# SwitchBoard_MP3.net
KiCad netlist of a schematic drawn in EAGLE
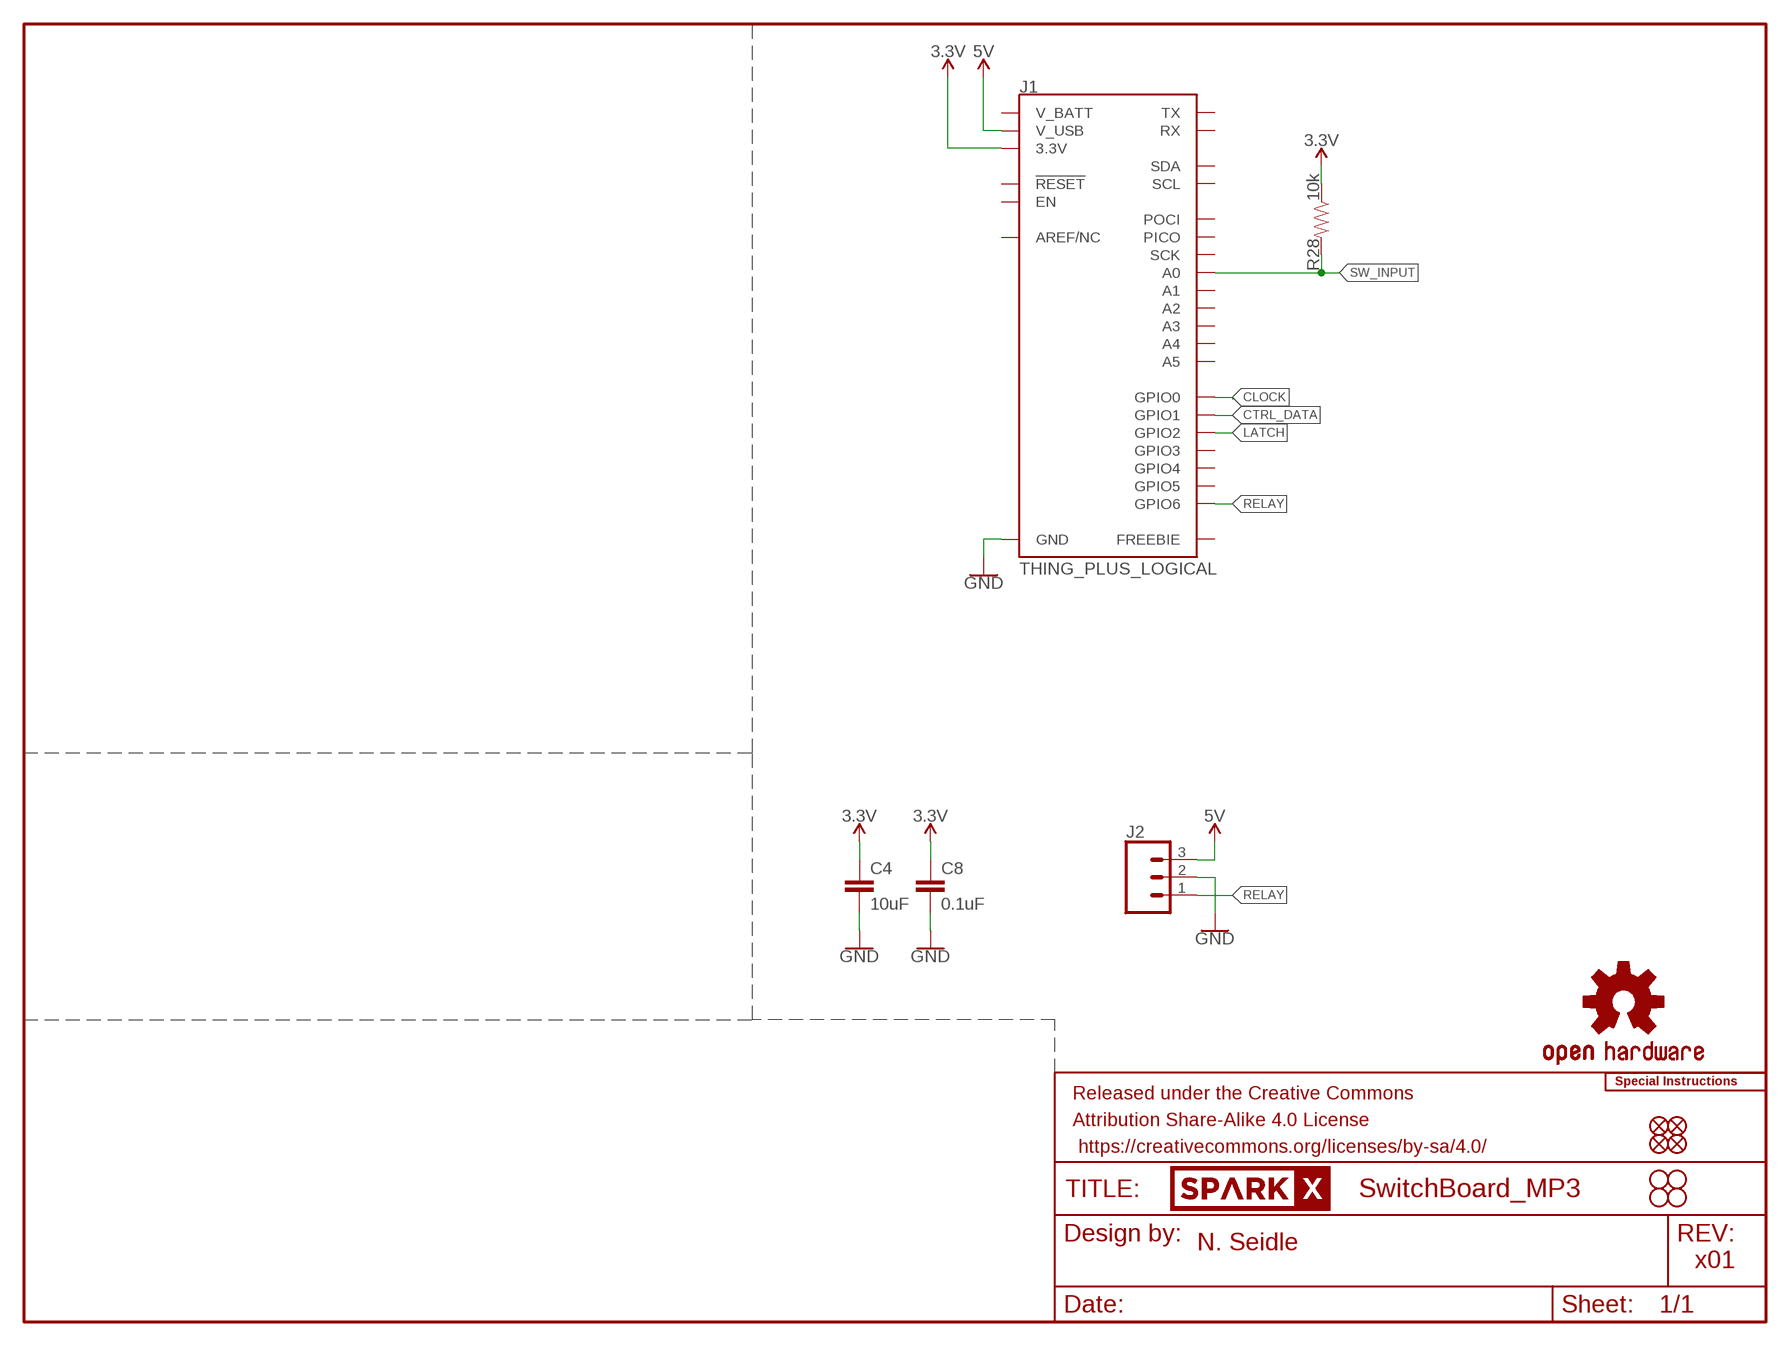
[diagram p0: schematic, sheet 1, part 1 of 2]
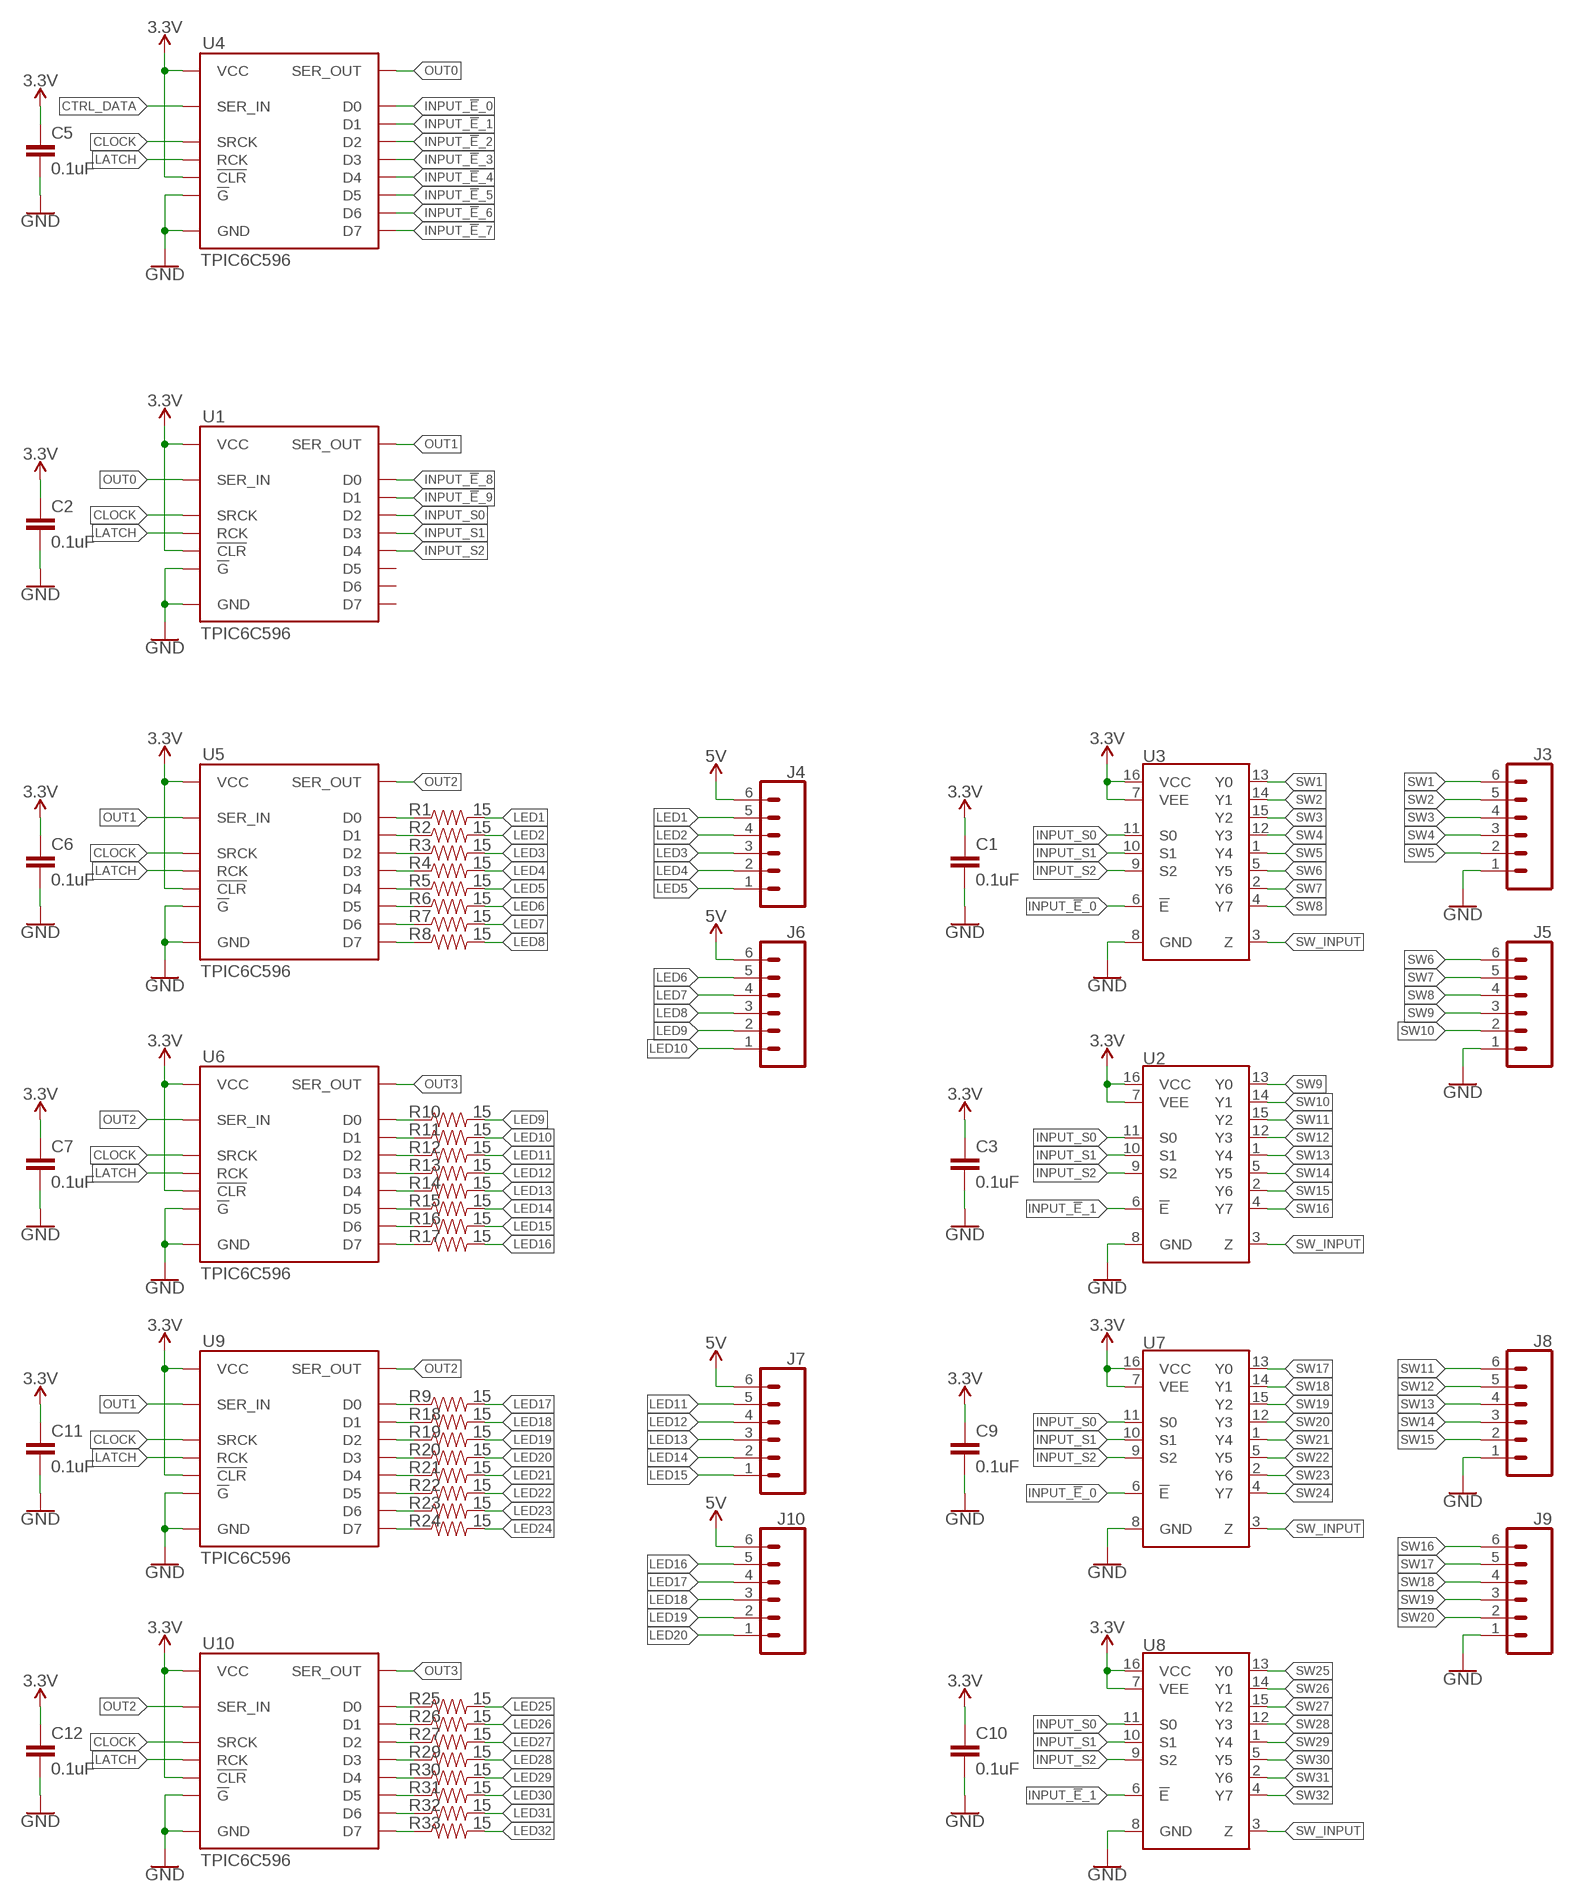
[diagram p1: schematic, sheet 1, part 2 of 2]

(export (version "E")
  (design (tool "Eeschema 10.0.6"))
  (components
    (comp (ref "C1")
      (value "0.1uF")
      (footprint "eagle-import:0603")
      (libsource (lib "eagle-import") (part "0.1UF-0603-25V-10%-X7R-WE"))
    )
    (comp (ref "C2")
      (value "0.1uF")
      (footprint "eagle-import:0603")
      (libsource (lib "eagle-import") (part "0.1UF-0603-25V-10%-X7R-WE"))
    )
    (comp (ref "C3")
      (value "0.1uF")
      (footprint "eagle-import:0603")
      (libsource (lib "eagle-import") (part "0.1UF-0603-25V-10%-X7R-WE"))
    )
    (comp (ref "C4")
      (value "10uF")
      (footprint "eagle-import:0805")
      (libsource (lib "eagle-import") (part "10UF-0805-25V-10%"))
    )
    (comp (ref "C5")
      (value "0.1uF")
      (footprint "eagle-import:0603")
      (libsource (lib "eagle-import") (part "0.1UF-0603-25V-10%-X7R-WE"))
    )
    (comp (ref "C6")
      (value "0.1uF")
      (footprint "eagle-import:0603")
      (libsource (lib "eagle-import") (part "0.1UF-0603-25V-10%-X7R-WE"))
    )
    (comp (ref "C7")
      (value "0.1uF")
      (footprint "eagle-import:0603")
      (libsource (lib "eagle-import") (part "0.1UF-0603-25V-10%-X7R-WE"))
    )
    (comp (ref "C8")
      (value "0.1uF")
      (footprint "eagle-import:0603")
      (libsource (lib "eagle-import") (part "0.1UF-0603-25V-10%-X7R-WE"))
    )
    (comp (ref "C9")
      (value "0.1uF")
      (footprint "eagle-import:0603")
      (libsource (lib "eagle-import") (part "0.1UF-0603-25V-10%-X7R-WE"))
    )
    (comp (ref "C10")
      (value "0.1uF")
      (footprint "eagle-import:0603")
      (libsource (lib "eagle-import") (part "0.1UF-0603-25V-10%-X7R-WE"))
    )
    (comp (ref "C11")
      (value "0.1uF")
      (footprint "eagle-import:0603")
      (libsource (lib "eagle-import") (part "0.1UF-0603-25V-10%-X7R-WE"))
    )
    (comp (ref "C12")
      (value "0.1uF")
      (footprint "eagle-import:0603")
      (libsource (lib "eagle-import") (part "0.1UF-0603-25V-10%-X7R-WE"))
    )
    (comp (ref "FD1")
      (value "FIDUCIAL1X2")
      (footprint "eagle-import:FIDUCIAL-1X2")
      (libsource (lib "eagle-import") (part "FIDUCIAL1X2"))
    )
    (comp (ref "FD2")
      (value "FIDUCIAL1X2")
      (footprint "eagle-import:FIDUCIAL-1X2")
      (libsource (lib "eagle-import") (part "FIDUCIAL1X2"))
    )
    (comp (ref "FD3")
      (value "FIDUCIAL1X2")
      (footprint "eagle-import:FIDUCIAL-1X2")
      (libsource (lib "eagle-import") (part "FIDUCIAL1X2"))
    )
    (comp (ref "FD4")
      (value "FIDUCIAL1X2")
      (footprint "eagle-import:FIDUCIAL-1X2")
      (libsource (lib "eagle-import") (part "FIDUCIAL1X2"))
    )
    (comp (ref "FRAME1")
      (value "FRAME-LETTER")
      (footprint "eagle-import:CREATIVE_COMMONS")
      (libsource (lib "eagle-import") (part "FRAME-LETTER"))
    )
    (comp (ref "H1")
      (value "STAND-OFF")
      (footprint "eagle-import:STAND-OFF")
      (libsource (lib "eagle-import") (part "STAND-OFF"))
    )
    (comp (ref "H2")
      (value "STAND-OFF")
      (footprint "eagle-import:STAND-OFF")
      (libsource (lib "eagle-import") (part "STAND-OFF"))
    )
    (comp (ref "H3")
      (value "STAND-OFF")
      (footprint "eagle-import:STAND-OFF")
      (libsource (lib "eagle-import") (part "STAND-OFF"))
    )
    (comp (ref "H4")
      (value "STAND-OFF")
      (footprint "eagle-import:STAND-OFF")
      (libsource (lib "eagle-import") (part "STAND-OFF"))
    )
    (comp (ref "J1")
      (value "THING_PLUS_LOGICAL")
      (footprint "eagle-import:THING_PLUS")
      (libsource (lib "eagle-import") (part "THING_PLUS_LOGICAL"))
    )
    (comp (ref "J2")
      (value "CONN_03JST-PTH-NS")
      (footprint "eagle-import:JST-3-PTH-NS")
      (libsource (lib "eagle-import") (part "CONN_03JST-PTH-NS"))
    )
    (comp (ref "J3")
      (value "CONN_06JST-SMD-LOCKING")
      (footprint "eagle-import:JST-6-SMD-1.25MM-LOCKING")
      (libsource (lib "eagle-import") (part "CONN_06JST-SMD-LOCKING"))
    )
    (comp (ref "J4")
      (value "CONN_06JST-SMD-LOCKING")
      (footprint "eagle-import:JST-6-SMD-1.25MM-LOCKING")
      (libsource (lib "eagle-import") (part "CONN_06JST-SMD-LOCKING"))
    )
    (comp (ref "J5")
      (value "CONN_06JST-SMD-LOCKING")
      (footprint "eagle-import:JST-6-SMD-1.25MM-LOCKING")
      (libsource (lib "eagle-import") (part "CONN_06JST-SMD-LOCKING"))
    )
    (comp (ref "J6")
      (value "CONN_06JST-SMD-LOCKING")
      (footprint "eagle-import:JST-6-SMD-1.25MM-LOCKING")
      (libsource (lib "eagle-import") (part "CONN_06JST-SMD-LOCKING"))
    )
    (comp (ref "J7")
      (value "CONN_06JST-SMD-LOCKING")
      (footprint "eagle-import:JST-6-SMD-1.25MM-LOCKING")
      (libsource (lib "eagle-import") (part "CONN_06JST-SMD-LOCKING"))
    )
    (comp (ref "J8")
      (value "CONN_06JST-SMD-LOCKING")
      (footprint "eagle-import:JST-6-SMD-1.25MM-LOCKING")
      (libsource (lib "eagle-import") (part "CONN_06JST-SMD-LOCKING"))
    )
    (comp (ref "J9")
      (value "CONN_06JST-SMD-LOCKING")
      (footprint "eagle-import:JST-6-SMD-1.25MM-LOCKING")
      (libsource (lib "eagle-import") (part "CONN_06JST-SMD-LOCKING"))
    )
    (comp (ref "J10")
      (value "CONN_06JST-SMD-LOCKING")
      (footprint "eagle-import:JST-6-SMD-1.25MM-LOCKING")
      (libsource (lib "eagle-import") (part "CONN_06JST-SMD-LOCKING"))
    )
    (comp (ref "LOGO1")
      (value "SPECIAL_INSTRUCTIONS-ORDERING")
      (footprint "eagle-import:ORDERING_INSTRUCTIONS")
      (libsource (lib "eagle-import") (part "SPECIAL_INSTRUCTIONS-ORDERING"))
    )
    (comp (ref "LOGO2")
      (value "OSHW-LOGOS")
      (footprint "eagle-import:OSHW-LOGO-S")
      (libsource (lib "eagle-import") (part "OSHW-LOGOS"))
    )
    (comp (ref "R1")
      (value "15")
      (footprint "eagle-import:0603")
      (libsource (lib "eagle-import") (part "15OHM-0603-1/10W-1%"))
    )
    (comp (ref "R2")
      (value "15")
      (footprint "eagle-import:0603")
      (libsource (lib "eagle-import") (part "15OHM-0603-1/10W-1%"))
    )
    (comp (ref "R3")
      (value "15")
      (footprint "eagle-import:0603")
      (libsource (lib "eagle-import") (part "15OHM-0603-1/10W-1%"))
    )
    (comp (ref "R4")
      (value "15")
      (footprint "eagle-import:0603")
      (libsource (lib "eagle-import") (part "15OHM-0603-1/10W-1%"))
    )
    (comp (ref "R5")
      (value "15")
      (footprint "eagle-import:0603")
      (libsource (lib "eagle-import") (part "15OHM-0603-1/10W-1%"))
    )
    (comp (ref "R6")
      (value "15")
      (footprint "eagle-import:0603")
      (libsource (lib "eagle-import") (part "15OHM-0603-1/10W-1%"))
    )
    (comp (ref "R7")
      (value "15")
      (footprint "eagle-import:0603")
      (libsource (lib "eagle-import") (part "15OHM-0603-1/10W-1%"))
    )
    (comp (ref "R8")
      (value "15")
      (footprint "eagle-import:0603")
      (libsource (lib "eagle-import") (part "15OHM-0603-1/10W-1%"))
    )
    (comp (ref "R9")
      (value "15")
      (footprint "eagle-import:0603")
      (libsource (lib "eagle-import") (part "15OHM-0603-1/10W-1%"))
    )
    (comp (ref "R10")
      (value "15")
      (footprint "eagle-import:0603")
      (libsource (lib "eagle-import") (part "15OHM-0603-1/10W-1%"))
    )
    (comp (ref "R11")
      (value "15")
      (footprint "eagle-import:0603")
      (libsource (lib "eagle-import") (part "15OHM-0603-1/10W-1%"))
    )
    (comp (ref "R12")
      (value "15")
      (footprint "eagle-import:0603")
      (libsource (lib "eagle-import") (part "15OHM-0603-1/10W-1%"))
    )
    (comp (ref "R13")
      (value "15")
      (footprint "eagle-import:0603")
      (libsource (lib "eagle-import") (part "15OHM-0603-1/10W-1%"))
    )
    (comp (ref "R14")
      (value "15")
      (footprint "eagle-import:0603")
      (libsource (lib "eagle-import") (part "15OHM-0603-1/10W-1%"))
    )
    (comp (ref "R15")
      (value "15")
      (footprint "eagle-import:0603")
      (libsource (lib "eagle-import") (part "15OHM-0603-1/10W-1%"))
    )
    (comp (ref "R16")
      (value "15")
      (footprint "eagle-import:0603")
      (libsource (lib "eagle-import") (part "15OHM-0603-1/10W-1%"))
    )
    (comp (ref "R17")
      (value "15")
      (footprint "eagle-import:0603")
      (libsource (lib "eagle-import") (part "15OHM-0603-1/10W-1%"))
    )
    (comp (ref "R18")
      (value "15")
      (footprint "eagle-import:0603")
      (libsource (lib "eagle-import") (part "15OHM-0603-1/10W-1%"))
    )
    (comp (ref "R19")
      (value "15")
      (footprint "eagle-import:0603")
      (libsource (lib "eagle-import") (part "15OHM-0603-1/10W-1%"))
    )
    (comp (ref "R20")
      (value "15")
      (footprint "eagle-import:0603")
      (libsource (lib "eagle-import") (part "15OHM-0603-1/10W-1%"))
    )
    (comp (ref "R21")
      (value "15")
      (footprint "eagle-import:0603")
      (libsource (lib "eagle-import") (part "15OHM-0603-1/10W-1%"))
    )
    (comp (ref "R22")
      (value "15")
      (footprint "eagle-import:0603")
      (libsource (lib "eagle-import") (part "15OHM-0603-1/10W-1%"))
    )
    (comp (ref "R23")
      (value "15")
      (footprint "eagle-import:0603")
      (libsource (lib "eagle-import") (part "15OHM-0603-1/10W-1%"))
    )
    (comp (ref "R24")
      (value "15")
      (footprint "eagle-import:0603")
      (libsource (lib "eagle-import") (part "15OHM-0603-1/10W-1%"))
    )
    (comp (ref "R25")
      (value "15")
      (footprint "eagle-import:0603")
      (libsource (lib "eagle-import") (part "15OHM-0603-1/10W-1%"))
    )
    (comp (ref "R26")
      (value "15")
      (footprint "eagle-import:0603")
      (libsource (lib "eagle-import") (part "15OHM-0603-1/10W-1%"))
    )
    (comp (ref "R27")
      (value "15")
      (footprint "eagle-import:0603")
      (libsource (lib "eagle-import") (part "15OHM-0603-1/10W-1%"))
    )
    (comp (ref "R28")
      (value "10k")
      (footprint "eagle-import:0603")
      (libsource (lib "eagle-import") (part "10KOHM-0603-1/10W-1%"))
    )
    (comp (ref "R29")
      (value "15")
      (footprint "eagle-import:0603")
      (libsource (lib "eagle-import") (part "15OHM-0603-1/10W-1%"))
    )
    (comp (ref "R30")
      (value "15")
      (footprint "eagle-import:0603")
      (libsource (lib "eagle-import") (part "15OHM-0603-1/10W-1%"))
    )
    (comp (ref "R31")
      (value "15")
      (footprint "eagle-import:0603")
      (libsource (lib "eagle-import") (part "15OHM-0603-1/10W-1%"))
    )
    (comp (ref "R32")
      (value "15")
      (footprint "eagle-import:0603")
      (libsource (lib "eagle-import") (part "15OHM-0603-1/10W-1%"))
    )
    (comp (ref "R33")
      (value "15")
      (footprint "eagle-import:0603")
      (libsource (lib "eagle-import") (part "15OHM-0603-1/10W-1%"))
    )
    (comp (ref "U$1")
      (value "SPARKX-LOGO4")
      (footprint "eagle-import:SPARKX-MEDIUM")
      (libsource (lib "eagle-import") (part "SPARKX-LOGO4"))
    )
    (comp (ref "U1")
      (value "TPIC6C596")
      (footprint "eagle-import:SO016")
      (libsource (lib "eagle-import") (part "TPIC6C596SOIC"))
    )
    (comp (ref "U2")
      (value "744051")
      (footprint "eagle-import:SO16")
      (libsource (lib "eagle-import") (part "744051"))
    )
    (comp (ref "U3")
      (value "744051")
      (footprint "eagle-import:SO16")
      (libsource (lib "eagle-import") (part "744051"))
    )
    (comp (ref "U4")
      (value "TPIC6C596")
      (footprint "eagle-import:SO016")
      (libsource (lib "eagle-import") (part "TPIC6C596SOIC"))
    )
    (comp (ref "U5")
      (value "TPIC6C596")
      (footprint "eagle-import:SO016")
      (libsource (lib "eagle-import") (part "TPIC6C596SOIC"))
    )
    (comp (ref "U6")
      (value "TPIC6C596")
      (footprint "eagle-import:SO016")
      (libsource (lib "eagle-import") (part "TPIC6C596SOIC"))
    )
    (comp (ref "U7")
      (value "744051")
      (footprint "eagle-import:SO16")
      (libsource (lib "eagle-import") (part "744051"))
    )
    (comp (ref "U8")
      (value "744051")
      (footprint "eagle-import:SO16")
      (libsource (lib "eagle-import") (part "744051"))
    )
    (comp (ref "U9")
      (value "TPIC6C596")
      (footprint "eagle-import:SO016")
      (libsource (lib "eagle-import") (part "TPIC6C596SOIC"))
    )
    (comp (ref "U10")
      (value "TPIC6C596")
      (footprint "eagle-import:SO016")
      (libsource (lib "eagle-import") (part "TPIC6C596SOIC"))
    )
  )
  (nets
    (net (code "1") (name "/INPUT_~{E}_0") (class "Default")
      (node (ref "U3") (pin "6") (pinfunction "~{E}_6") (pintype "bidirectional"))
      (node (ref "U4") (pin "3") (pinfunction "D0_3") (pintype "output"))
      (node (ref "U7") (pin "6") (pinfunction "~{E}_6") (pintype "bidirectional"))
    )
    (net (code "2") (name "/INPUT_~{E}_1") (class "Default")
      (node (ref "U2") (pin "6") (pinfunction "~{E}_6") (pintype "bidirectional"))
      (node (ref "U4") (pin "4") (pinfunction "D1_4") (pintype "output"))
      (node (ref "U8") (pin "6") (pinfunction "~{E}_6") (pintype "bidirectional"))
    )
    (net (code "3") (name "/INPUT_~{E}_2") (class "Default")
      (node (ref "U4") (pin "5") (pinfunction "D2_5") (pintype "output"))
    )
    (net (code "4") (name "/INPUT_~{E}_3") (class "Default")
      (node (ref "U4") (pin "6") (pinfunction "D3_6") (pintype "output"))
    )
    (net (code "5") (name "/INPUT_~{E}_4") (class "Default")
      (node (ref "U4") (pin "11") (pinfunction "D4_11") (pintype "output"))
    )
    (net (code "6") (name "/INPUT_~{E}_5") (class "Default")
      (node (ref "U4") (pin "12") (pinfunction "D5_12") (pintype "output"))
    )
    (net (code "7") (name "/INPUT_~{E}_6") (class "Default")
      (node (ref "U4") (pin "13") (pinfunction "D6_13") (pintype "output"))
    )
    (net (code "8") (name "/INPUT_~{E}_7") (class "Default")
      (node (ref "U4") (pin "14") (pinfunction "D7_14") (pintype "output"))
    )
    (net (code "9") (name "/INPUT_~{E}_8") (class "Default")
      (node (ref "U1") (pin "3") (pinfunction "D0_3") (pintype "output"))
    )
    (net (code "10") (name "/INPUT_~{E}_9") (class "Default")
      (node (ref "U1") (pin "4") (pinfunction "D1_4") (pintype "output"))
    )
    (net (code "11") (name "3.3V") (class "Default")
      (node (ref "C1") (pin "1") (pinfunction "1_1") (pintype "passive"))
      (node (ref "C10") (pin "1") (pinfunction "1_1") (pintype "passive"))
      (node (ref "C11") (pin "1") (pinfunction "1_1") (pintype "passive"))
      (node (ref "C12") (pin "1") (pinfunction "1_1") (pintype "passive"))
      (node (ref "C2") (pin "1") (pinfunction "1_1") (pintype "passive"))
      (node (ref "C3") (pin "1") (pinfunction "1_1") (pintype "passive"))
      (node (ref "C4") (pin "1") (pinfunction "1_1") (pintype "passive"))
      (node (ref "C5") (pin "1") (pinfunction "1_1") (pintype "passive"))
      (node (ref "C6") (pin "1") (pinfunction "1_1") (pintype "passive"))
      (node (ref "C7") (pin "1") (pinfunction "1_1") (pintype "passive"))
      (node (ref "C8") (pin "1") (pinfunction "1_1") (pintype "passive"))
      (node (ref "C9") (pin "1") (pinfunction "1_1") (pintype "passive"))
      (node (ref "J1") (pin "27") (pinfunction "3.3V_27") (pintype "bidirectional"))
      (node (ref "R28") (pin "1") (pinfunction "1_1") (pintype "passive"))
      (node (ref "U1") (pin "1") (pinfunction "VCC_1") (pintype "power_in"))
      (node (ref "U1") (pin "7") (pinfunction "~{CLR}_7") (pintype "input"))
      (node (ref "U10") (pin "1") (pinfunction "VCC_1") (pintype "power_in"))
      (node (ref "U10") (pin "7") (pinfunction "~{CLR}_7") (pintype "input"))
      (node (ref "U2") (pin "16") (pinfunction "VCC_16") (pintype "bidirectional"))
      (node (ref "U2") (pin "7") (pinfunction "VEE_7") (pintype "bidirectional"))
      (node (ref "U3") (pin "16") (pinfunction "VCC_16") (pintype "bidirectional"))
      (node (ref "U3") (pin "7") (pinfunction "VEE_7") (pintype "bidirectional"))
      (node (ref "U4") (pin "1") (pinfunction "VCC_1") (pintype "power_in"))
      (node (ref "U4") (pin "7") (pinfunction "~{CLR}_7") (pintype "input"))
      (node (ref "U5") (pin "1") (pinfunction "VCC_1") (pintype "power_in"))
      (node (ref "U5") (pin "7") (pinfunction "~{CLR}_7") (pintype "input"))
      (node (ref "U6") (pin "1") (pinfunction "VCC_1") (pintype "power_in"))
      (node (ref "U6") (pin "7") (pinfunction "~{CLR}_7") (pintype "input"))
      (node (ref "U7") (pin "16") (pinfunction "VCC_16") (pintype "bidirectional"))
      (node (ref "U7") (pin "7") (pinfunction "VEE_7") (pintype "bidirectional"))
      (node (ref "U8") (pin "16") (pinfunction "VCC_16") (pintype "bidirectional"))
      (node (ref "U8") (pin "7") (pinfunction "VEE_7") (pintype "bidirectional"))
      (node (ref "U9") (pin "1") (pinfunction "VCC_1") (pintype "power_in"))
      (node (ref "U9") (pin "7") (pinfunction "~{CLR}_7") (pintype "input"))
    )
    (net (code "12") (name "5V") (class "Default")
      (node (ref "J1") (pin "10") (pinfunction "V_USB_10") (pintype "bidirectional"))
      (node (ref "J10") (pin "6") (pinfunction "6_6") (pintype "passive"))
      (node (ref "J2") (pin "3") (pinfunction "3_3") (pintype "passive"))
      (node (ref "J4") (pin "6") (pinfunction "6_6") (pintype "passive"))
      (node (ref "J6") (pin "6") (pinfunction "6_6") (pintype "passive"))
      (node (ref "J7") (pin "6") (pinfunction "6_6") (pintype "passive"))
    )
    (net (code "13") (name "CLOCK") (class "Default")
      (node (ref "J1") (pin "9") (pinfunction "GPIO0_9") (pintype "bidirectional"))
      (node (ref "U1") (pin "15") (pinfunction "SRCK_15") (pintype "input"))
      (node (ref "U10") (pin "15") (pinfunction "SRCK_15") (pintype "input"))
      (node (ref "U4") (pin "15") (pinfunction "SRCK_15") (pintype "input"))
      (node (ref "U5") (pin "15") (pinfunction "SRCK_15") (pintype "input"))
      (node (ref "U6") (pin "15") (pinfunction "SRCK_15") (pintype "input"))
      (node (ref "U9") (pin "15") (pinfunction "SRCK_15") (pintype "input"))
    )
    (net (code "14") (name "CTRL_DATA") (class "Default")
      (node (ref "J1") (pin "8") (pinfunction "GPIO1_8") (pintype "bidirectional"))
      (node (ref "U4") (pin "2") (pinfunction "SER_IN_2") (pintype "input"))
    )
    (net (code "15") (name "GND") (class "Default")
      (node (ref "C1") (pin "2") (pinfunction "2_2") (pintype "passive"))
      (node (ref "C10") (pin "2") (pinfunction "2_2") (pintype "passive"))
      (node (ref "C11") (pin "2") (pinfunction "2_2") (pintype "passive"))
      (node (ref "C12") (pin "2") (pinfunction "2_2") (pintype "passive"))
      (node (ref "C2") (pin "2") (pinfunction "2_2") (pintype "passive"))
      (node (ref "C3") (pin "2") (pinfunction "2_2") (pintype "passive"))
      (node (ref "C4") (pin "2") (pinfunction "2_2") (pintype "passive"))
      (node (ref "C5") (pin "2") (pinfunction "2_2") (pintype "passive"))
      (node (ref "C6") (pin "2") (pinfunction "2_2") (pintype "passive"))
      (node (ref "C7") (pin "2") (pinfunction "2_2") (pintype "passive"))
      (node (ref "C8") (pin "2") (pinfunction "2_2") (pintype "passive"))
      (node (ref "C9") (pin "2") (pinfunction "2_2") (pintype "passive"))
      (node (ref "J1") (pin "25") (pinfunction "GND_25") (pintype "bidirectional"))
      (node (ref "J2") (pin "2") (pinfunction "2_2") (pintype "passive"))
      (node (ref "J3") (pin "1") (pinfunction "1_1") (pintype "passive"))
      (node (ref "J5") (pin "1") (pinfunction "1_1") (pintype "passive"))
      (node (ref "J8") (pin "1") (pinfunction "1_1") (pintype "passive"))
      (node (ref "J9") (pin "1") (pinfunction "1_1") (pintype "passive"))
      (node (ref "U1") (pin "16") (pinfunction "GND_16") (pintype "power_in"))
      (node (ref "U1") (pin "8") (pinfunction "~{G}_8") (pintype "input"))
      (node (ref "U10") (pin "16") (pinfunction "GND_16") (pintype "power_in"))
      (node (ref "U10") (pin "8") (pinfunction "~{G}_8") (pintype "input"))
      (node (ref "U2") (pin "8") (pinfunction "GND_8") (pintype "bidirectional"))
      (node (ref "U3") (pin "8") (pinfunction "GND_8") (pintype "bidirectional"))
      (node (ref "U4") (pin "16") (pinfunction "GND_16") (pintype "power_in"))
      (node (ref "U4") (pin "8") (pinfunction "~{G}_8") (pintype "input"))
      (node (ref "U5") (pin "16") (pinfunction "GND_16") (pintype "power_in"))
      (node (ref "U5") (pin "8") (pinfunction "~{G}_8") (pintype "input"))
      (node (ref "U6") (pin "16") (pinfunction "GND_16") (pintype "power_in"))
      (node (ref "U6") (pin "8") (pinfunction "~{G}_8") (pintype "input"))
      (node (ref "U7") (pin "8") (pinfunction "GND_8") (pintype "bidirectional"))
      (node (ref "U8") (pin "8") (pinfunction "GND_8") (pintype "bidirectional"))
      (node (ref "U9") (pin "16") (pinfunction "GND_16") (pintype "power_in"))
      (node (ref "U9") (pin "8") (pinfunction "~{G}_8") (pintype "input"))
    )
    (net (code "16") (name "INPUT_S0") (class "Default")
      (node (ref "U1") (pin "5") (pinfunction "D2_5") (pintype "output"))
      (node (ref "U2") (pin "11") (pinfunction "S0_11") (pintype "bidirectional"))
      (node (ref "U3") (pin "11") (pinfunction "S0_11") (pintype "bidirectional"))
      (node (ref "U7") (pin "11") (pinfunction "S0_11") (pintype "bidirectional"))
      (node (ref "U8") (pin "11") (pinfunction "S0_11") (pintype "bidirectional"))
    )
    (net (code "17") (name "INPUT_S1") (class "Default")
      (node (ref "U1") (pin "6") (pinfunction "D3_6") (pintype "output"))
      (node (ref "U2") (pin "10") (pinfunction "S1_10") (pintype "bidirectional"))
      (node (ref "U3") (pin "10") (pinfunction "S1_10") (pintype "bidirectional"))
      (node (ref "U7") (pin "10") (pinfunction "S1_10") (pintype "bidirectional"))
      (node (ref "U8") (pin "10") (pinfunction "S1_10") (pintype "bidirectional"))
    )
    (net (code "18") (name "INPUT_S2") (class "Default")
      (node (ref "U1") (pin "11") (pinfunction "D4_11") (pintype "output"))
      (node (ref "U2") (pin "9") (pinfunction "S2_9") (pintype "bidirectional"))
      (node (ref "U3") (pin "9") (pinfunction "S2_9") (pintype "bidirectional"))
      (node (ref "U7") (pin "9") (pinfunction "S2_9") (pintype "bidirectional"))
      (node (ref "U8") (pin "9") (pinfunction "S2_9") (pintype "bidirectional"))
    )
    (net (code "19") (name "LATCH") (class "Default")
      (node (ref "J1") (pin "7") (pinfunction "GPIO2_7") (pintype "bidirectional"))
      (node (ref "U1") (pin "10") (pinfunction "RCK_10") (pintype "input"))
      (node (ref "U10") (pin "10") (pinfunction "RCK_10") (pintype "input"))
      (node (ref "U4") (pin "10") (pinfunction "RCK_10") (pintype "input"))
      (node (ref "U5") (pin "10") (pinfunction "RCK_10") (pintype "input"))
      (node (ref "U6") (pin "10") (pinfunction "RCK_10") (pintype "input"))
      (node (ref "U9") (pin "10") (pinfunction "RCK_10") (pintype "input"))
    )
    (net (code "20") (name "LED1") (class "Default")
      (node (ref "J4") (pin "5") (pinfunction "5_5") (pintype "passive"))
      (node (ref "R1") (pin "2") (pinfunction "2_2") (pintype "passive"))
    )
    (net (code "21") (name "LED2") (class "Default")
      (node (ref "J4") (pin "4") (pinfunction "4_4") (pintype "passive"))
      (node (ref "R2") (pin "2") (pinfunction "2_2") (pintype "passive"))
    )
    (net (code "22") (name "LED3") (class "Default")
      (node (ref "J4") (pin "3") (pinfunction "3_3") (pintype "passive"))
      (node (ref "R3") (pin "2") (pinfunction "2_2") (pintype "passive"))
    )
    (net (code "23") (name "LED4") (class "Default")
      (node (ref "J4") (pin "2") (pinfunction "2_2") (pintype "passive"))
      (node (ref "R4") (pin "2") (pinfunction "2_2") (pintype "passive"))
    )
    (net (code "24") (name "LED5") (class "Default")
      (node (ref "J4") (pin "1") (pinfunction "1_1") (pintype "passive"))
      (node (ref "R5") (pin "2") (pinfunction "2_2") (pintype "passive"))
    )
    (net (code "25") (name "LED6") (class "Default")
      (node (ref "J6") (pin "5") (pinfunction "5_5") (pintype "passive"))
      (node (ref "R6") (pin "2") (pinfunction "2_2") (pintype "passive"))
    )
    (net (code "26") (name "LED7") (class "Default")
      (node (ref "J6") (pin "4") (pinfunction "4_4") (pintype "passive"))
      (node (ref "R7") (pin "2") (pinfunction "2_2") (pintype "passive"))
    )
    (net (code "27") (name "LED8") (class "Default")
      (node (ref "J6") (pin "3") (pinfunction "3_3") (pintype "passive"))
      (node (ref "R8") (pin "2") (pinfunction "2_2") (pintype "passive"))
    )
    (net (code "28") (name "LED9") (class "Default")
      (node (ref "J6") (pin "2") (pinfunction "2_2") (pintype "passive"))
      (node (ref "R10") (pin "2") (pinfunction "2_2") (pintype "passive"))
    )
    (net (code "29") (name "LED10") (class "Default")
      (node (ref "J6") (pin "1") (pinfunction "1_1") (pintype "passive"))
      (node (ref "R11") (pin "2") (pinfunction "2_2") (pintype "passive"))
    )
    (net (code "30") (name "LED11") (class "Default")
      (node (ref "J7") (pin "5") (pinfunction "5_5") (pintype "passive"))
      (node (ref "R12") (pin "2") (pinfunction "2_2") (pintype "passive"))
    )
    (net (code "31") (name "LED12") (class "Default")
      (node (ref "J7") (pin "4") (pinfunction "4_4") (pintype "passive"))
      (node (ref "R13") (pin "2") (pinfunction "2_2") (pintype "passive"))
    )
    (net (code "32") (name "LED13") (class "Default")
      (node (ref "J7") (pin "3") (pinfunction "3_3") (pintype "passive"))
      (node (ref "R14") (pin "2") (pinfunction "2_2") (pintype "passive"))
    )
    (net (code "33") (name "LED14") (class "Default")
      (node (ref "J7") (pin "2") (pinfunction "2_2") (pintype "passive"))
      (node (ref "R15") (pin "2") (pinfunction "2_2") (pintype "passive"))
    )
    (net (code "34") (name "LED15") (class "Default")
      (node (ref "J7") (pin "1") (pinfunction "1_1") (pintype "passive"))
      (node (ref "R16") (pin "2") (pinfunction "2_2") (pintype "passive"))
    )
    (net (code "35") (name "LED16") (class "Default")
      (node (ref "J10") (pin "5") (pinfunction "5_5") (pintype "passive"))
      (node (ref "R17") (pin "2") (pinfunction "2_2") (pintype "passive"))
    )
    (net (code "36") (name "LED17") (class "Default")
      (node (ref "J10") (pin "4") (pinfunction "4_4") (pintype "passive"))
      (node (ref "R9") (pin "2") (pinfunction "2_2") (pintype "passive"))
    )
    (net (code "37") (name "LED18") (class "Default")
      (node (ref "J10") (pin "3") (pinfunction "3_3") (pintype "passive"))
      (node (ref "R18") (pin "2") (pinfunction "2_2") (pintype "passive"))
    )
    (net (code "38") (name "LED19") (class "Default")
      (node (ref "J10") (pin "2") (pinfunction "2_2") (pintype "passive"))
      (node (ref "R19") (pin "2") (pinfunction "2_2") (pintype "passive"))
    )
    (net (code "39") (name "LED20") (class "Default")
      (node (ref "J10") (pin "1") (pinfunction "1_1") (pintype "passive"))
      (node (ref "R20") (pin "2") (pinfunction "2_2") (pintype "passive"))
    )
    (net (code "40") (name "LED21") (class "Default")
      (node (ref "R21") (pin "2") (pinfunction "2_2") (pintype "passive"))
    )
    (net (code "41") (name "LED22") (class "Default")
      (node (ref "R22") (pin "2") (pinfunction "2_2") (pintype "passive"))
    )
    (net (code "42") (name "LED23") (class "Default")
      (node (ref "R23") (pin "2") (pinfunction "2_2") (pintype "passive"))
    )
    (net (code "43") (name "LED24") (class "Default")
      (node (ref "R24") (pin "2") (pinfunction "2_2") (pintype "passive"))
    )
    (net (code "44") (name "LED25") (class "Default")
      (node (ref "R25") (pin "2") (pinfunction "2_2") (pintype "passive"))
    )
    (net (code "45") (name "LED26") (class "Default")
      (node (ref "R26") (pin "2") (pinfunction "2_2") (pintype "passive"))
    )
    (net (code "46") (name "LED27") (class "Default")
      (node (ref "R27") (pin "2") (pinfunction "2_2") (pintype "passive"))
    )
    (net (code "47") (name "LED28") (class "Default")
      (node (ref "R29") (pin "2") (pinfunction "2_2") (pintype "passive"))
    )
    (net (code "48") (name "LED29") (class "Default")
      (node (ref "R30") (pin "2") (pinfunction "2_2") (pintype "passive"))
    )
    (net (code "49") (name "LED30") (class "Default")
      (node (ref "R31") (pin "2") (pinfunction "2_2") (pintype "passive"))
    )
    (net (code "50") (name "LED31") (class "Default")
      (node (ref "R32") (pin "2") (pinfunction "2_2") (pintype "passive"))
    )
    (net (code "51") (name "LED32") (class "Default")
      (node (ref "R33") (pin "2") (pinfunction "2_2") (pintype "passive"))
    )
    (net (code "52") (name "Net-(U5-D0)") (class "Default")
      (node (ref "R1") (pin "1") (pinfunction "1_1") (pintype "passive"))
      (node (ref "U5") (pin "3") (pinfunction "D0_3") (pintype "output"))
    )
    (net (code "53") (name "Net-(U5-D1)") (class "Default")
      (node (ref "R2") (pin "1") (pinfunction "1_1") (pintype "passive"))
      (node (ref "U5") (pin "4") (pinfunction "D1_4") (pintype "output"))
    )
    (net (code "54") (name "Net-(U5-D2)") (class "Default")
      (node (ref "R3") (pin "1") (pinfunction "1_1") (pintype "passive"))
      (node (ref "U5") (pin "5") (pinfunction "D2_5") (pintype "output"))
    )
    (net (code "55") (name "Net-(U5-D3)") (class "Default")
      (node (ref "R4") (pin "1") (pinfunction "1_1") (pintype "passive"))
      (node (ref "U5") (pin "6") (pinfunction "D3_6") (pintype "output"))
    )
    (net (code "56") (name "Net-(U5-D4)") (class "Default")
      (node (ref "R5") (pin "1") (pinfunction "1_1") (pintype "passive"))
      (node (ref "U5") (pin "11") (pinfunction "D4_11") (pintype "output"))
    )
    (net (code "57") (name "Net-(U5-D5)") (class "Default")
      (node (ref "R6") (pin "1") (pinfunction "1_1") (pintype "passive"))
      (node (ref "U5") (pin "12") (pinfunction "D5_12") (pintype "output"))
    )
    (net (code "58") (name "Net-(U5-D6)") (class "Default")
      (node (ref "R7") (pin "1") (pinfunction "1_1") (pintype "passive"))
      (node (ref "U5") (pin "13") (pinfunction "D6_13") (pintype "output"))
    )
    (net (code "59") (name "Net-(U5-D7)") (class "Default")
      (node (ref "R8") (pin "1") (pinfunction "1_1") (pintype "passive"))
      (node (ref "U5") (pin "14") (pinfunction "D7_14") (pintype "output"))
    )
    (net (code "60") (name "Net-(U6-D0)") (class "Default")
      (node (ref "R10") (pin "1") (pinfunction "1_1") (pintype "passive"))
      (node (ref "U6") (pin "3") (pinfunction "D0_3") (pintype "output"))
    )
    (net (code "61") (name "Net-(U6-D1)") (class "Default")
      (node (ref "R11") (pin "1") (pinfunction "1_1") (pintype "passive"))
      (node (ref "U6") (pin "4") (pinfunction "D1_4") (pintype "output"))
    )
    (net (code "62") (name "Net-(U6-D2)") (class "Default")
      (node (ref "R12") (pin "1") (pinfunction "1_1") (pintype "passive"))
      (node (ref "U6") (pin "5") (pinfunction "D2_5") (pintype "output"))
    )
    (net (code "63") (name "Net-(U6-D3)") (class "Default")
      (node (ref "R13") (pin "1") (pinfunction "1_1") (pintype "passive"))
      (node (ref "U6") (pin "6") (pinfunction "D3_6") (pintype "output"))
    )
    (net (code "64") (name "Net-(U6-D4)") (class "Default")
      (node (ref "R14") (pin "1") (pinfunction "1_1") (pintype "passive"))
      (node (ref "U6") (pin "11") (pinfunction "D4_11") (pintype "output"))
    )
    (net (code "65") (name "Net-(U6-D5)") (class "Default")
      (node (ref "R15") (pin "1") (pinfunction "1_1") (pintype "passive"))
      (node (ref "U6") (pin "12") (pinfunction "D5_12") (pintype "output"))
    )
    (net (code "66") (name "Net-(U6-D6)") (class "Default")
      (node (ref "R16") (pin "1") (pinfunction "1_1") (pintype "passive"))
      (node (ref "U6") (pin "13") (pinfunction "D6_13") (pintype "output"))
    )
    (net (code "67") (name "Net-(U6-D7)") (class "Default")
      (node (ref "R17") (pin "1") (pinfunction "1_1") (pintype "passive"))
      (node (ref "U6") (pin "14") (pinfunction "D7_14") (pintype "output"))
    )
    (net (code "68") (name "Net-(U9-D0)") (class "Default")
      (node (ref "R9") (pin "1") (pinfunction "1_1") (pintype "passive"))
      (node (ref "U9") (pin "3") (pinfunction "D0_3") (pintype "output"))
    )
    (net (code "69") (name "Net-(U9-D1)") (class "Default")
      (node (ref "R18") (pin "1") (pinfunction "1_1") (pintype "passive"))
      (node (ref "U9") (pin "4") (pinfunction "D1_4") (pintype "output"))
    )
    (net (code "70") (name "Net-(U9-D2)") (class "Default")
      (node (ref "R19") (pin "1") (pinfunction "1_1") (pintype "passive"))
      (node (ref "U9") (pin "5") (pinfunction "D2_5") (pintype "output"))
    )
    (net (code "71") (name "Net-(U9-D3)") (class "Default")
      (node (ref "R20") (pin "1") (pinfunction "1_1") (pintype "passive"))
      (node (ref "U9") (pin "6") (pinfunction "D3_6") (pintype "output"))
    )
    (net (code "72") (name "Net-(U9-D4)") (class "Default")
      (node (ref "R21") (pin "1") (pinfunction "1_1") (pintype "passive"))
      (node (ref "U9") (pin "11") (pinfunction "D4_11") (pintype "output"))
    )
    (net (code "73") (name "Net-(U9-D5)") (class "Default")
      (node (ref "R22") (pin "1") (pinfunction "1_1") (pintype "passive"))
      (node (ref "U9") (pin "12") (pinfunction "D5_12") (pintype "output"))
    )
    (net (code "74") (name "Net-(U9-D6)") (class "Default")
      (node (ref "R23") (pin "1") (pinfunction "1_1") (pintype "passive"))
      (node (ref "U9") (pin "13") (pinfunction "D6_13") (pintype "output"))
    )
    (net (code "75") (name "Net-(U9-D7)") (class "Default")
      (node (ref "R24") (pin "1") (pinfunction "1_1") (pintype "passive"))
      (node (ref "U9") (pin "14") (pinfunction "D7_14") (pintype "output"))
    )
    (net (code "76") (name "Net-(U10-D0)") (class "Default")
      (node (ref "R25") (pin "1") (pinfunction "1_1") (pintype "passive"))
      (node (ref "U10") (pin "3") (pinfunction "D0_3") (pintype "output"))
    )
    (net (code "77") (name "Net-(U10-D1)") (class "Default")
      (node (ref "R26") (pin "1") (pinfunction "1_1") (pintype "passive"))
      (node (ref "U10") (pin "4") (pinfunction "D1_4") (pintype "output"))
    )
    (net (code "78") (name "Net-(U10-D2)") (class "Default")
      (node (ref "R27") (pin "1") (pinfunction "1_1") (pintype "passive"))
      (node (ref "U10") (pin "5") (pinfunction "D2_5") (pintype "output"))
    )
    (net (code "79") (name "Net-(U10-D3)") (class "Default")
      (node (ref "R29") (pin "1") (pinfunction "1_1") (pintype "passive"))
      (node (ref "U10") (pin "6") (pinfunction "D3_6") (pintype "output"))
    )
    (net (code "80") (name "Net-(U10-D4)") (class "Default")
      (node (ref "R30") (pin "1") (pinfunction "1_1") (pintype "passive"))
      (node (ref "U10") (pin "11") (pinfunction "D4_11") (pintype "output"))
    )
    (net (code "81") (name "Net-(U10-D5)") (class "Default")
      (node (ref "R31") (pin "1") (pinfunction "1_1") (pintype "passive"))
      (node (ref "U10") (pin "12") (pinfunction "D5_12") (pintype "output"))
    )
    (net (code "82") (name "Net-(U10-D6)") (class "Default")
      (node (ref "R32") (pin "1") (pinfunction "1_1") (pintype "passive"))
      (node (ref "U10") (pin "13") (pinfunction "D6_13") (pintype "output"))
    )
    (net (code "83") (name "Net-(U10-D7)") (class "Default")
      (node (ref "R33") (pin "1") (pinfunction "1_1") (pintype "passive"))
      (node (ref "U10") (pin "14") (pinfunction "D7_14") (pintype "output"))
    )
    (net (code "84") (name "OUT0") (class "Default")
      (node (ref "U1") (pin "2") (pinfunction "SER_IN_2") (pintype "input"))
      (node (ref "U4") (pin "9") (pinfunction "SER_OUT_9") (pintype "output"))
    )
    (net (code "85") (name "OUT1") (class "Default")
      (node (ref "U1") (pin "9") (pinfunction "SER_OUT_9") (pintype "output"))
      (node (ref "U5") (pin "2") (pinfunction "SER_IN_2") (pintype "input"))
      (node (ref "U9") (pin "2") (pinfunction "SER_IN_2") (pintype "input"))
    )
    (net (code "86") (name "OUT2") (class "Default")
      (node (ref "U10") (pin "2") (pinfunction "SER_IN_2") (pintype "input"))
      (node (ref "U5") (pin "9") (pinfunction "SER_OUT_9") (pintype "output"))
      (node (ref "U6") (pin "2") (pinfunction "SER_IN_2") (pintype "input"))
      (node (ref "U9") (pin "9") (pinfunction "SER_OUT_9") (pintype "output"))
    )
    (net (code "87") (name "OUT3") (class "Default")
      (node (ref "U10") (pin "9") (pinfunction "SER_OUT_9") (pintype "output"))
      (node (ref "U6") (pin "9") (pinfunction "SER_OUT_9") (pintype "output"))
    )
    (net (code "88") (name "RELAY") (class "Default")
      (node (ref "J1") (pin "3") (pinfunction "GPIO6_3") (pintype "bidirectional"))
      (node (ref "J2") (pin "1") (pinfunction "1_1") (pintype "passive"))
    )
    (net (code "89") (name "SW1") (class "Default")
      (node (ref "J3") (pin "6") (pinfunction "6_6") (pintype "passive"))
      (node (ref "U3") (pin "13") (pinfunction "Y0_13") (pintype "bidirectional"))
    )
    (net (code "90") (name "SW2") (class "Default")
      (node (ref "J3") (pin "5") (pinfunction "5_5") (pintype "passive"))
      (node (ref "U3") (pin "14") (pinfunction "Y1_14") (pintype "bidirectional"))
    )
    (net (code "91") (name "SW3") (class "Default")
      (node (ref "J3") (pin "4") (pinfunction "4_4") (pintype "passive"))
      (node (ref "U3") (pin "15") (pinfunction "Y2_15") (pintype "bidirectional"))
    )
    (net (code "92") (name "SW4") (class "Default")
      (node (ref "J3") (pin "3") (pinfunction "3_3") (pintype "passive"))
      (node (ref "U3") (pin "12") (pinfunction "Y3_12") (pintype "bidirectional"))
    )
    (net (code "93") (name "SW5") (class "Default")
      (node (ref "J3") (pin "2") (pinfunction "2_2") (pintype "passive"))
      (node (ref "U3") (pin "1") (pinfunction "Y4_1") (pintype "bidirectional"))
    )
    (net (code "94") (name "SW6") (class "Default")
      (node (ref "J5") (pin "6") (pinfunction "6_6") (pintype "passive"))
      (node (ref "U3") (pin "5") (pinfunction "Y5_5") (pintype "bidirectional"))
    )
    (net (code "95") (name "SW7") (class "Default")
      (node (ref "J5") (pin "5") (pinfunction "5_5") (pintype "passive"))
      (node (ref "U3") (pin "2") (pinfunction "Y6_2") (pintype "bidirectional"))
    )
    (net (code "96") (name "SW8") (class "Default")
      (node (ref "J5") (pin "4") (pinfunction "4_4") (pintype "passive"))
      (node (ref "U3") (pin "4") (pinfunction "Y7_4") (pintype "bidirectional"))
    )
    (net (code "97") (name "SW9") (class "Default")
      (node (ref "J5") (pin "3") (pinfunction "3_3") (pintype "passive"))
      (node (ref "U2") (pin "13") (pinfunction "Y0_13") (pintype "bidirectional"))
    )
    (net (code "98") (name "SW10") (class "Default")
      (node (ref "J5") (pin "2") (pinfunction "2_2") (pintype "passive"))
      (node (ref "U2") (pin "14") (pinfunction "Y1_14") (pintype "bidirectional"))
    )
    (net (code "99") (name "SW11") (class "Default")
      (node (ref "J8") (pin "6") (pinfunction "6_6") (pintype "passive"))
      (node (ref "U2") (pin "15") (pinfunction "Y2_15") (pintype "bidirectional"))
    )
    (net (code "100") (name "SW12") (class "Default")
      (node (ref "J8") (pin "5") (pinfunction "5_5") (pintype "passive"))
      (node (ref "U2") (pin "12") (pinfunction "Y3_12") (pintype "bidirectional"))
    )
    (net (code "101") (name "SW13") (class "Default")
      (node (ref "J8") (pin "4") (pinfunction "4_4") (pintype "passive"))
      (node (ref "U2") (pin "1") (pinfunction "Y4_1") (pintype "bidirectional"))
    )
    (net (code "102") (name "SW14") (class "Default")
      (node (ref "J8") (pin "3") (pinfunction "3_3") (pintype "passive"))
      (node (ref "U2") (pin "5") (pinfunction "Y5_5") (pintype "bidirectional"))
    )
    (net (code "103") (name "SW15") (class "Default")
      (node (ref "J8") (pin "2") (pinfunction "2_2") (pintype "passive"))
      (node (ref "U2") (pin "2") (pinfunction "Y6_2") (pintype "bidirectional"))
    )
    (net (code "104") (name "SW16") (class "Default")
      (node (ref "J9") (pin "6") (pinfunction "6_6") (pintype "passive"))
      (node (ref "U2") (pin "4") (pinfunction "Y7_4") (pintype "bidirectional"))
    )
    (net (code "105") (name "SW17") (class "Default")
      (node (ref "J9") (pin "5") (pinfunction "5_5") (pintype "passive"))
      (node (ref "U7") (pin "13") (pinfunction "Y0_13") (pintype "bidirectional"))
    )
    (net (code "106") (name "SW18") (class "Default")
      (node (ref "J9") (pin "4") (pinfunction "4_4") (pintype "passive"))
      (node (ref "U7") (pin "14") (pinfunction "Y1_14") (pintype "bidirectional"))
    )
    (net (code "107") (name "SW19") (class "Default")
      (node (ref "J9") (pin "3") (pinfunction "3_3") (pintype "passive"))
      (node (ref "U7") (pin "15") (pinfunction "Y2_15") (pintype "bidirectional"))
    )
    (net (code "108") (name "SW20") (class "Default")
      (node (ref "J9") (pin "2") (pinfunction "2_2") (pintype "passive"))
      (node (ref "U7") (pin "12") (pinfunction "Y3_12") (pintype "bidirectional"))
    )
    (net (code "109") (name "SW21") (class "Default")
      (node (ref "U7") (pin "1") (pinfunction "Y4_1") (pintype "bidirectional"))
    )
    (net (code "110") (name "SW22") (class "Default")
      (node (ref "U7") (pin "5") (pinfunction "Y5_5") (pintype "bidirectional"))
    )
    (net (code "111") (name "SW23") (class "Default")
      (node (ref "U7") (pin "2") (pinfunction "Y6_2") (pintype "bidirectional"))
    )
    (net (code "112") (name "SW24") (class "Default")
      (node (ref "U7") (pin "4") (pinfunction "Y7_4") (pintype "bidirectional"))
    )
    (net (code "113") (name "SW25") (class "Default")
      (node (ref "U8") (pin "13") (pinfunction "Y0_13") (pintype "bidirectional"))
    )
    (net (code "114") (name "SW26") (class "Default")
      (node (ref "U8") (pin "14") (pinfunction "Y1_14") (pintype "bidirectional"))
    )
    (net (code "115") (name "SW27") (class "Default")
      (node (ref "U8") (pin "15") (pinfunction "Y2_15") (pintype "bidirectional"))
    )
    (net (code "116") (name "SW28") (class "Default")
      (node (ref "U8") (pin "12") (pinfunction "Y3_12") (pintype "bidirectional"))
    )
    (net (code "117") (name "SW29") (class "Default")
      (node (ref "U8") (pin "1") (pinfunction "Y4_1") (pintype "bidirectional"))
    )
    (net (code "118") (name "SW30") (class "Default")
      (node (ref "U8") (pin "5") (pinfunction "Y5_5") (pintype "bidirectional"))
    )
    (net (code "119") (name "SW31") (class "Default")
      (node (ref "U8") (pin "2") (pinfunction "Y6_2") (pintype "bidirectional"))
    )
    (net (code "120") (name "SW32") (class "Default")
      (node (ref "U8") (pin "4") (pinfunction "Y7_4") (pintype "bidirectional"))
    )
    (net (code "121") (name "SW_INPUT") (class "Default")
      (node (ref "J1") (pin "24") (pinfunction "A0_24") (pintype "bidirectional"))
      (node (ref "R28") (pin "2") (pinfunction "2_2") (pintype "passive"))
      (node (ref "U2") (pin "3") (pinfunction "Z_3") (pintype "bidirectional"))
      (node (ref "U3") (pin "3") (pinfunction "Z_3") (pintype "bidirectional"))
      (node (ref "U7") (pin "3") (pinfunction "Z_3") (pintype "bidirectional"))
      (node (ref "U8") (pin "3") (pinfunction "Z_3") (pintype "bidirectional"))
    )
    (net (code "122") (name "unconnected-(J1-A1-Pad23)") (class "Default")
      (node (ref "J1") (pin "23") (pinfunction "A1_23") (pintype "bidirectional"))
    )
    (net (code "123") (name "unconnected-(J1-A2-Pad22)") (class "Default")
      (node (ref "J1") (pin "22") (pinfunction "A2_22") (pintype "bidirectional"))
    )
    (net (code "124") (name "unconnected-(J1-A3-Pad21)") (class "Default")
      (node (ref "J1") (pin "21") (pinfunction "A3_21") (pintype "bidirectional"))
    )
    (net (code "125") (name "unconnected-(J1-A4-Pad20)") (class "Default")
      (node (ref "J1") (pin "20") (pinfunction "A4_20") (pintype "bidirectional"))
    )
    (net (code "126") (name "unconnected-(J1-A5-Pad19)") (class "Default")
      (node (ref "J1") (pin "19") (pinfunction "A5_19") (pintype "bidirectional"))
    )
    (net (code "127") (name "unconnected-(J1-AREF{slash}NC-Pad26)") (class "Default")
      (node (ref "J1") (pin "26") (pinfunction "AREF/NC_26") (pintype "bidirectional"))
    )
    (net (code "128") (name "unconnected-(J1-EN-Pad11)") (class "Default")
      (node (ref "J1") (pin "11") (pinfunction "EN_11") (pintype "bidirectional"))
    )
    (net (code "129") (name "unconnected-(J1-FREEBIE-Pad13)") (class "Default")
      (node (ref "J1") (pin "13") (pinfunction "FREEBIE_13") (pintype "bidirectional"))
    )
    (net (code "130") (name "unconnected-(J1-GPIO3-Pad6)") (class "Default")
      (node (ref "J1") (pin "6") (pinfunction "GPIO3_6") (pintype "bidirectional"))
    )
    (net (code "131") (name "unconnected-(J1-GPIO4-Pad5)") (class "Default")
      (node (ref "J1") (pin "5") (pinfunction "GPIO4_5") (pintype "bidirectional"))
    )
    (net (code "132") (name "unconnected-(J1-GPIO5-Pad4)") (class "Default")
      (node (ref "J1") (pin "4") (pinfunction "GPIO5_4") (pintype "bidirectional"))
    )
    (net (code "133") (name "unconnected-(J1-PICO-Pad17)") (class "Default")
      (node (ref "J1") (pin "17") (pinfunction "PICO_17") (pintype "bidirectional"))
    )
    (net (code "134") (name "unconnected-(J1-POCI-Pad16)") (class "Default")
      (node (ref "J1") (pin "16") (pinfunction "POCI_16") (pintype "bidirectional"))
    )
    (net (code "135") (name "unconnected-(J1-RX-Pad15)") (class "Default")
      (node (ref "J1") (pin "15") (pinfunction "RX_15") (pintype "bidirectional"))
    )
    (net (code "136") (name "unconnected-(J1-SCK-Pad18)") (class "Default")
      (node (ref "J1") (pin "18") (pinfunction "SCK_18") (pintype "bidirectional"))
    )
    (net (code "137") (name "unconnected-(J1-SCL-Pad2)") (class "Default")
      (node (ref "J1") (pin "2") (pinfunction "SCL_2") (pintype "bidirectional"))
    )
    (net (code "138") (name "unconnected-(J1-SDA-Pad1)") (class "Default")
      (node (ref "J1") (pin "1") (pinfunction "SDA_1") (pintype "bidirectional"))
    )
    (net (code "139") (name "unconnected-(J1-TX-Pad14)") (class "Default")
      (node (ref "J1") (pin "14") (pinfunction "TX_14") (pintype "bidirectional"))
    )
    (net (code "140") (name "unconnected-(J1-V_BATT-Pad12)") (class "Default")
      (node (ref "J1") (pin "12") (pinfunction "V_BATT_12") (pintype "bidirectional"))
    )
    (net (code "141") (name "unconnected-(J1-~{RESET}-Pad28)") (class "Default")
      (node (ref "J1") (pin "28") (pinfunction "~{RESET}_28") (pintype "bidirectional"))
    )
    (net (code "142") (name "unconnected-(U1-D5-Pad12)") (class "Default")
      (node (ref "U1") (pin "12") (pinfunction "D5_12") (pintype "output"))
    )
    (net (code "143") (name "unconnected-(U1-D6-Pad13)") (class "Default")
      (node (ref "U1") (pin "13") (pinfunction "D6_13") (pintype "output"))
    )
    (net (code "144") (name "unconnected-(U1-D7-Pad14)") (class "Default")
      (node (ref "U1") (pin "14") (pinfunction "D7_14") (pintype "output"))
    )
  )
)
